# evpr_osh.net
KiCad netlist of a schematic drawn in EAGLE
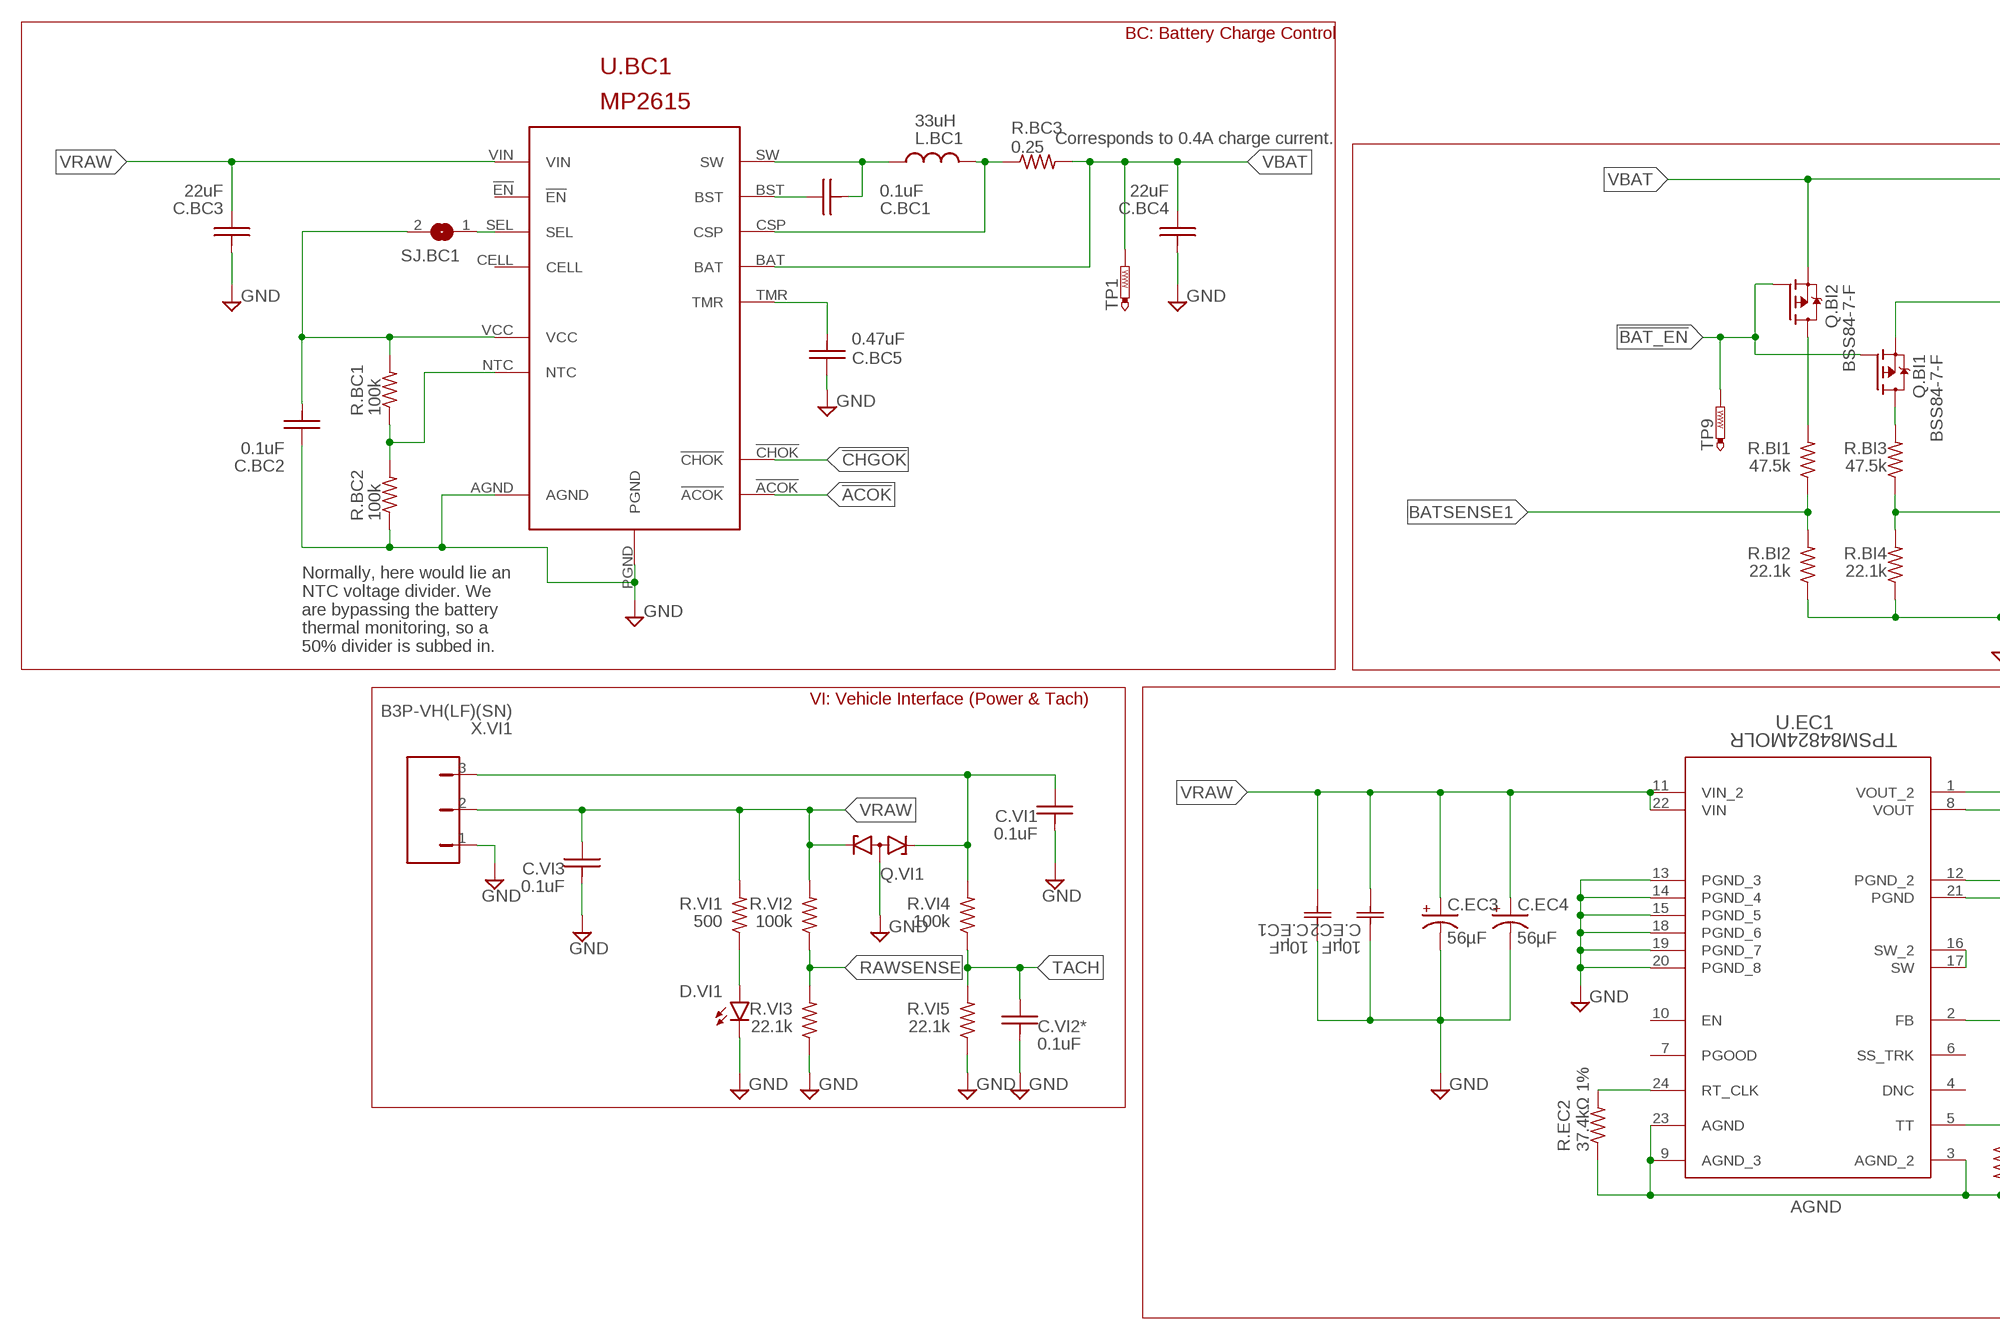
[diagram p0: schematic, sheet 1, part 1 of 2]
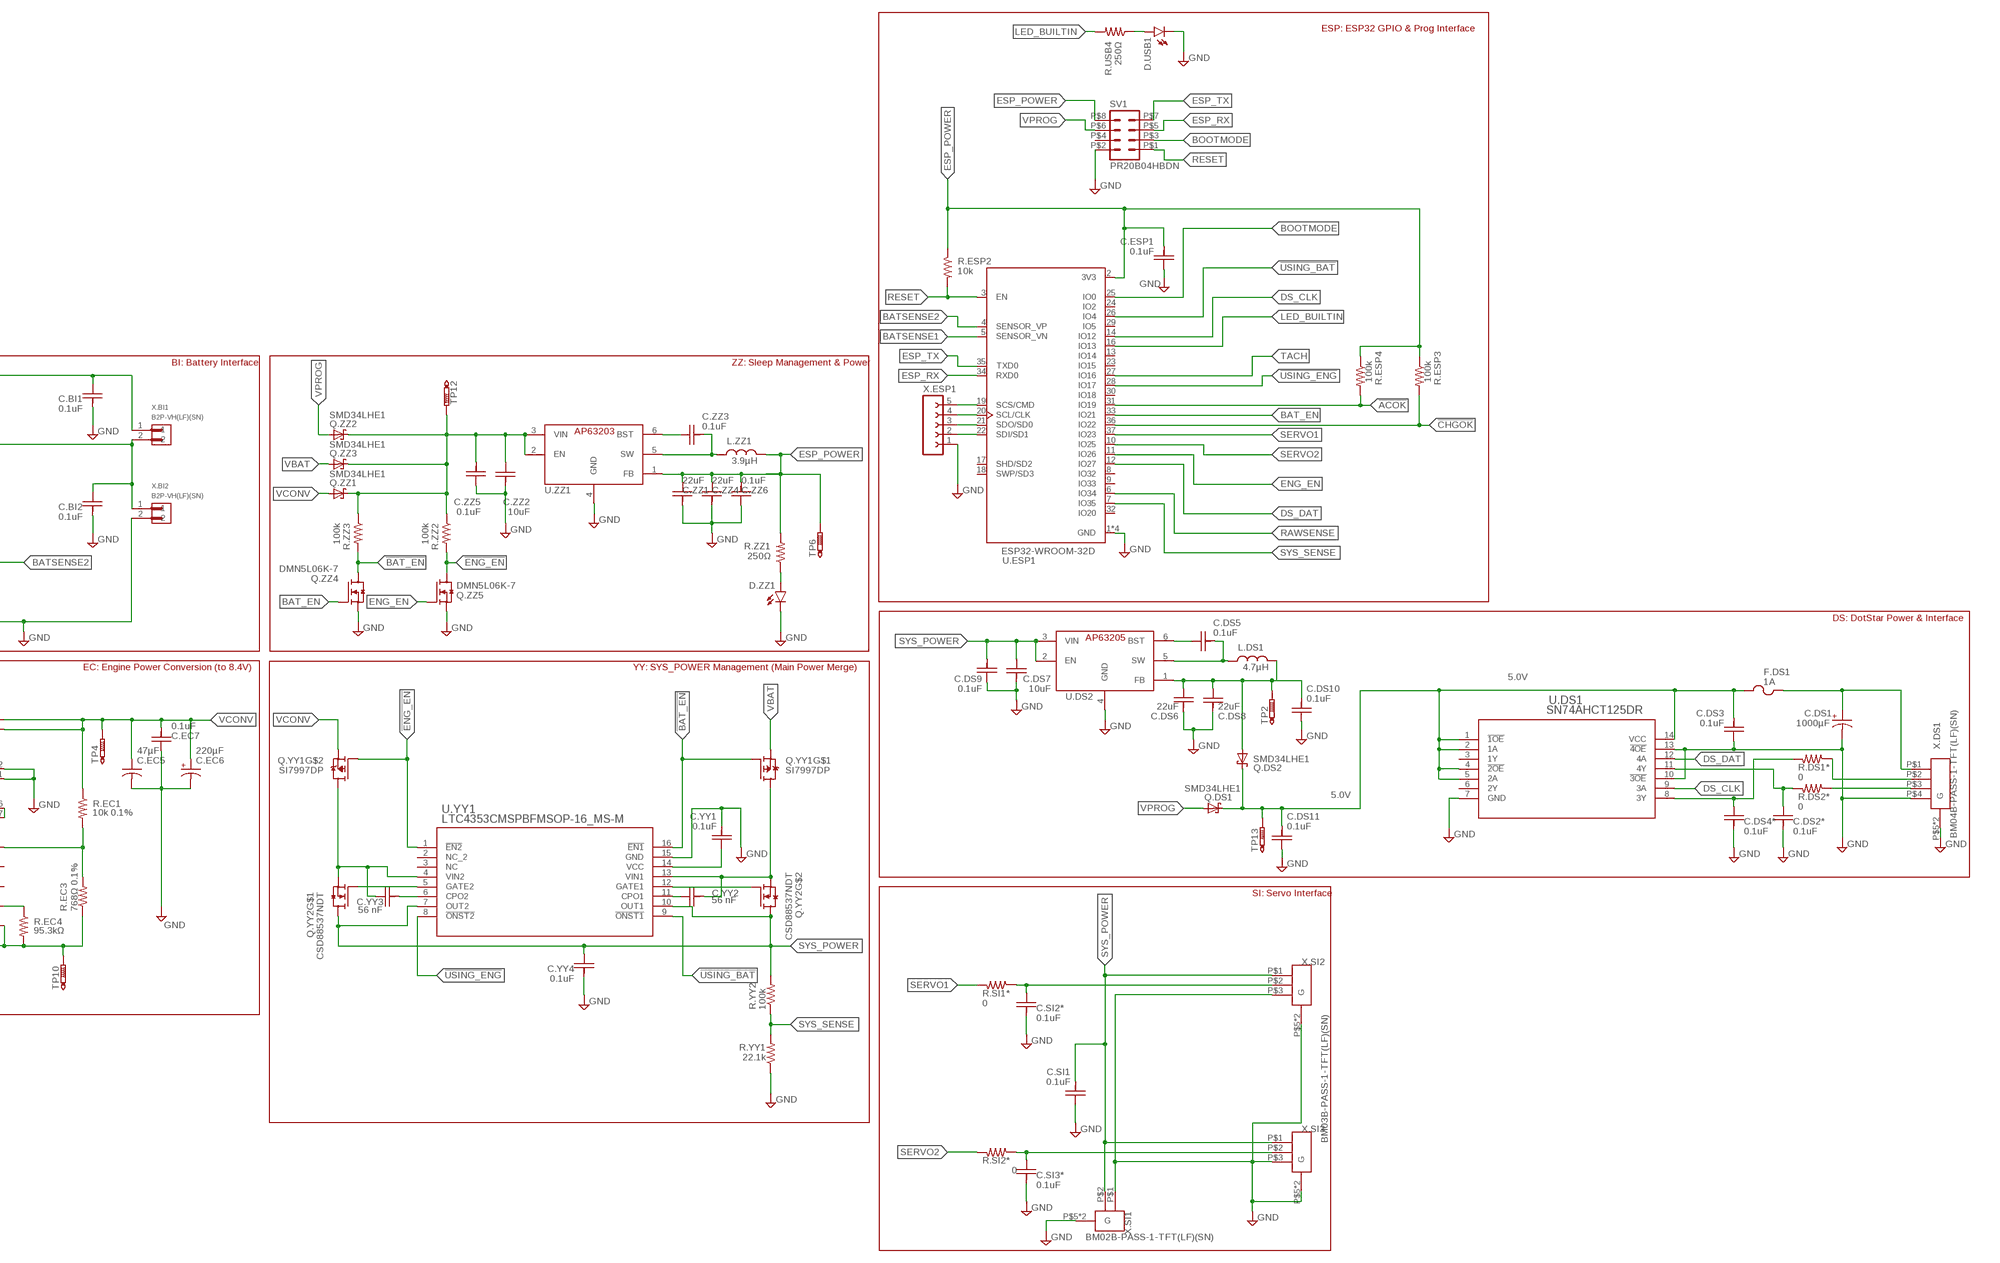
[diagram p1: schematic, sheet 1, part 2 of 2]

(export (version "E")
  (design (tool "Eeschema 10.0.6"))
  (components
    (comp (ref "C.BC1")
      (value "0.1uF")
      (footprint "eagle-import:C0603")
      (libsource (lib "eagle-import") (part "C0603"))
    )
    (comp (ref "C.BC2")
      (value "0.1uF")
      (footprint "eagle-import:C0603")
      (libsource (lib "eagle-import") (part "C0603"))
    )
    (comp (ref "C.BC3")
      (value "22uF")
      (footprint "eagle-import:C0603")
      (libsource (lib "eagle-import") (part "C0603"))
    )
    (comp (ref "C.BC4")
      (value "22uF")
      (footprint "eagle-import:C0603")
      (libsource (lib "eagle-import") (part "C0603"))
    )
    (comp (ref "C.BC5")
      (value "0.47uF")
      (footprint "eagle-import:C0603")
      (libsource (lib "eagle-import") (part "C0603"))
    )
    (comp (ref "C.BI1")
      (value "0.1uF")
      (footprint "eagle-import:C0603")
      (libsource (lib "eagle-import") (part "C0603"))
    )
    (comp (ref "C.BI2")
      (value "0.1uF")
      (footprint "eagle-import:C0603")
      (libsource (lib "eagle-import") (part "C0603"))
    )
    (comp (ref "C.DS1")
      (value "1000µF")
      (footprint "eagle-import:810RADCAN")
      (libsource (lib "eagle-import") (part "810RADCAP"))
    )
    (comp (ref "C.DS2*")
      (value "0.1uF")
      (footprint "eagle-import:C0603")
      (libsource (lib "eagle-import") (part "C0603"))
    )
    (comp (ref "C.DS3")
      (value "0.1uF")
      (footprint "eagle-import:C0603")
      (libsource (lib "eagle-import") (part "C0603"))
    )
    (comp (ref "C.DS4*")
      (value "0.1uF")
      (footprint "eagle-import:C0603")
      (libsource (lib "eagle-import") (part "C0603"))
    )
    (comp (ref "C.DS5")
      (value "0.1uF")
      (footprint "eagle-import:C0603")
      (libsource (lib "eagle-import") (part "C0603"))
    )
    (comp (ref "C.DS6")
      (value "22uF")
      (footprint "eagle-import:C0603")
      (libsource (lib "eagle-import") (part "C0603"))
    )
    (comp (ref "C.DS7")
      (value "10uF")
      (footprint "eagle-import:C0603")
      (libsource (lib "eagle-import") (part "C0603"))
    )
    (comp (ref "C.DS8")
      (value "22uF")
      (footprint "eagle-import:C0603")
      (libsource (lib "eagle-import") (part "C0603"))
    )
    (comp (ref "C.DS9")
      (value "0.1uF")
      (footprint "eagle-import:C0603")
      (libsource (lib "eagle-import") (part "C0603"))
    )
    (comp (ref "C.DS10")
      (value "0.1uF")
      (footprint "eagle-import:C0603")
      (libsource (lib "eagle-import") (part "C0603"))
    )
    (comp (ref "C.DS11")
      (value "0.1uF")
      (footprint "eagle-import:C0603")
      (libsource (lib "eagle-import") (part "C0603"))
    )
    (comp (ref "C.EC1")
      (value "10µF")
      (footprint "eagle-import:CAP_3225")
      (libsource (lib "eagle-import") (part "C3225X7R1E106K250AC"))
    )
    (comp (ref "C.EC2")
      (value "10µF")
      (footprint "eagle-import:CAP_3225")
      (libsource (lib "eagle-import") (part "C3225X7R1E106K250AC"))
    )
    (comp (ref "C.EC3")
      (value "56µF")
      (footprint "eagle-import:OSCON_SVPF_6.3MM")
      (libsource (lib "eagle-import") (part "6.3MMCAP"))
    )
    (comp (ref "C.EC4")
      (value "56µF")
      (footprint "eagle-import:OSCON_SVPF_6.3MM")
      (libsource (lib "eagle-import") (part "6.3MMCAP"))
    )
    (comp (ref "C.EC5")
      (value "47µF")
      (footprint "eagle-import:C1210")
      (libsource (lib "eagle-import") (part "C-USC1210"))
    )
    (comp (ref "C.EC6")
      (value "220µF")
      (footprint "eagle-import:C6CYLCAP")
      (libsource (lib "eagle-import") (part "WURTH875115352003"))
    )
    (comp (ref "C.EC7")
      (value "0.1uF")
      (footprint "eagle-import:C0603")
      (libsource (lib "eagle-import") (part "C0603"))
    )
    (comp (ref "C.ESP1")
      (value "0.1uF")
      (footprint "eagle-import:C0603")
      (libsource (lib "eagle-import") (part "C0603"))
    )
    (comp (ref "C.SI1")
      (value "0.1uF")
      (footprint "eagle-import:C0603")
      (libsource (lib "eagle-import") (part "C0603"))
    )
    (comp (ref "C.SI2*")
      (value "0.1uF")
      (footprint "eagle-import:C0603")
      (libsource (lib "eagle-import") (part "C0603"))
    )
    (comp (ref "C.SI3*")
      (value "0.1uF")
      (footprint "eagle-import:C0603")
      (libsource (lib "eagle-import") (part "C0603"))
    )
    (comp (ref "C.VI1")
      (value "0.1uF")
      (footprint "eagle-import:C0603")
      (libsource (lib "eagle-import") (part "C0603"))
    )
    (comp (ref "C.VI2*")
      (value "0.1uF")
      (footprint "eagle-import:C0603")
      (libsource (lib "eagle-import") (part "C0603"))
    )
    (comp (ref "C.VI3")
      (value "0.1uF")
      (footprint "eagle-import:C0603")
      (libsource (lib "eagle-import") (part "C0603"))
    )
    (comp (ref "C.YY1")
      (value "0.1uF")
      (footprint "eagle-import:C0603")
      (libsource (lib "eagle-import") (part "C0603"))
    )
    (comp (ref "C.YY2")
      (value "56 nF")
      (footprint "eagle-import:C0603")
      (libsource (lib "eagle-import") (part "C0603"))
    )
    (comp (ref "C.YY3")
      (value "56 nF")
      (footprint "eagle-import:C0603")
      (libsource (lib "eagle-import") (part "C0603"))
    )
    (comp (ref "C.YY4")
      (value "0.1uF")
      (footprint "eagle-import:C0603")
      (libsource (lib "eagle-import") (part "C0603"))
    )
    (comp (ref "C.ZZ1")
      (value "22uF")
      (footprint "eagle-import:C0603")
      (libsource (lib "eagle-import") (part "C0603"))
    )
    (comp (ref "C.ZZ2")
      (value "10uF")
      (footprint "eagle-import:C0603")
      (libsource (lib "eagle-import") (part "C0603"))
    )
    (comp (ref "C.ZZ3")
      (value "0.1uF")
      (footprint "eagle-import:C0603")
      (libsource (lib "eagle-import") (part "C0603"))
    )
    (comp (ref "C.ZZ4")
      (value "22uF")
      (footprint "eagle-import:C0603")
      (libsource (lib "eagle-import") (part "C0603"))
    )
    (comp (ref "C.ZZ5")
      (value "0.1uF")
      (footprint "eagle-import:C0603")
      (libsource (lib "eagle-import") (part "C0603"))
    )
    (comp (ref "C.ZZ6")
      (value "0.1uF")
      (footprint "eagle-import:C0603")
      (libsource (lib "eagle-import") (part "C0603"))
    )
    (comp (ref "D.USB1")
      (value "LEDCHIP-LED0805")
      (footprint "eagle-import:CHIP-LED0805")
      (libsource (lib "eagle-import") (part "LEDCHIP-LED0805"))
    )
    (comp (ref "D.VI1")
      (value "LEDCHIP-LED0805")
      (footprint "eagle-import:CHIP-LED0805")
      (libsource (lib "eagle-import") (part "LEDCHIP-LED0805"))
    )
    (comp (ref "D.ZZ1")
      (value "LEDCHIP-LED0805")
      (footprint "eagle-import:CHIP-LED0805")
      (libsource (lib "eagle-import") (part "LEDCHIP-LED0805"))
    )
    (comp (ref "F.DS1")
      (value "1A")
      (footprint "eagle-import:C1-M")
      (fields (field (name "MANUFACTURER_PART_NUMBER") "C1Q 1"))
      (libsource (lib "eagle-import") (part "C1Q_1C1-M"))
    )
    (comp (ref "L.BC1")
      (value "33uH")
      (footprint "eagle-import:SRN5040TA")
      (libsource (lib "eagle-import") (part "SRN5040TA-330M"))
    )
    (comp (ref "L.DS1")
      (value "4.7µH")
      (footprint "eagle-import:SRR4818A-XXXX")
      (libsource (lib "eagle-import") (part "SRR4818A-XXXX"))
    )
    (comp (ref "L.ZZ1")
      (value "3.9µH")
      (footprint "eagle-import:SRR4818A-XXXX")
      (libsource (lib "eagle-import") (part "SRR4818A-XXXX"))
    )
    (comp (ref "Q.BI1")
      (value "BSS84-7-F")
      (footprint "eagle-import:SOT23")
      (libsource (lib "eagle-import") (part "BSS84-7-F"))
    )
    (comp (ref "Q.BI2")
      (value "BSS84-7-F")
      (footprint "eagle-import:SOT23")
      (libsource (lib "eagle-import") (part "BSS84-7-F"))
    )
    (comp (ref "Q.DS1")
      (value "SMD34LHE1")
      (footprint "eagle-import:SOD-123HE1")
      (libsource (lib "eagle-import") (part "SMD34LHE1"))
    )
    (comp (ref "Q.DS2")
      (value "SMD34LHE1")
      (footprint "eagle-import:SOD-123HE1")
      (libsource (lib "eagle-import") (part "SMD34LHE1"))
    )
    (comp (ref "Q.VI1")
      (value "VESD16A2-03G-G3-08")
      (footprint "eagle-import:SOT23")
      (libsource (lib "eagle-import") (part "VESD16A2-03G-G3-08"))
    )
    (comp (ref "Q.YY1")
      (value "SI7997DP")
      (footprint "eagle-import:POWERPAK_SO8DUAL")
      (libsource (lib "eagle-import") (part "SI7997DP"))
    )
    (comp (ref "Q.YY2")
      (value "CSD88537NDT")
      (footprint "eagle-import:SOIC8")
      (fields (field (name "COMPONENT") "CSD88537NDT"))
      (libsource (lib "eagle-import") (part "CSD88537NDT"))
    )
    (comp (ref "Q.ZZ1")
      (value "SMD34LHE1")
      (footprint "eagle-import:SOD-123HE1")
      (libsource (lib "eagle-import") (part "SMD34LHE1"))
    )
    (comp (ref "Q.ZZ2")
      (value "SMD34LHE1")
      (footprint "eagle-import:SOD-123HE1")
      (libsource (lib "eagle-import") (part "SMD34LHE1"))
    )
    (comp (ref "Q.ZZ3")
      (value "SMD34LHE1")
      (footprint "eagle-import:SOD-123HE1")
      (libsource (lib "eagle-import") (part "SMD34LHE1"))
    )
    (comp (ref "Q.ZZ4")
      (value "DMN5L06K-7")
      (footprint "eagle-import:SOT23")
      (libsource (lib "eagle-import") (part "DMN5L06K-7"))
    )
    (comp (ref "Q.ZZ5")
      (value "DMN5L06K-7")
      (footprint "eagle-import:SOT23")
      (libsource (lib "eagle-import") (part "DMN5L06K-7"))
    )
    (comp (ref "R.BC1")
      (value "100k")
      (footprint "eagle-import:R0603")
      (libsource (lib "eagle-import") (part "R0603"))
    )
    (comp (ref "R.BC2")
      (value "100k")
      (footprint "eagle-import:R0603")
      (libsource (lib "eagle-import") (part "R0603"))
    )
    (comp (ref "R.BC3")
      (value "0.25")
      (footprint "eagle-import:R0603")
      (libsource (lib "eagle-import") (part "R0603"))
    )
    (comp (ref "R.BI1")
      (value "47.5k")
      (footprint "eagle-import:R0603")
      (libsource (lib "eagle-import") (part "R0603"))
    )
    (comp (ref "R.BI2")
      (value "22.1k")
      (footprint "eagle-import:R0603")
      (libsource (lib "eagle-import") (part "R0603"))
    )
    (comp (ref "R.BI3")
      (value "47.5k")
      (footprint "eagle-import:R0603")
      (libsource (lib "eagle-import") (part "R0603"))
    )
    (comp (ref "R.BI4")
      (value "22.1k")
      (footprint "eagle-import:R0603")
      (libsource (lib "eagle-import") (part "R0603"))
    )
    (comp (ref "R.DS1*")
      (value "0")
      (footprint "eagle-import:R0603")
      (libsource (lib "eagle-import") (part "R0603"))
    )
    (comp (ref "R.DS2*")
      (value "0")
      (footprint "eagle-import:R0603")
      (libsource (lib "eagle-import") (part "R0603"))
    )
    (comp (ref "R.EC1")
      (value "10k 0.1%")
      (footprint "eagle-import:R0603")
      (libsource (lib "eagle-import") (part "R0603"))
    )
    (comp (ref "R.EC2")
      (value "37.4kΩ 1%")
      (footprint "eagle-import:R0603")
      (libsource (lib "eagle-import") (part "R0603"))
    )
    (comp (ref "R.EC3")
      (value "768Ω 0.1%")
      (footprint "eagle-import:R0603")
      (libsource (lib "eagle-import") (part "R0603"))
    )
    (comp (ref "R.EC4")
      (value "95.3kΩ")
      (footprint "eagle-import:R0603")
      (libsource (lib "eagle-import") (part "R0603"))
    )
    (comp (ref "R.ESP2")
      (value "10k")
      (footprint "eagle-import:R0603")
      (libsource (lib "eagle-import") (part "R0603"))
    )
    (comp (ref "R.ESP3")
      (value "100k")
      (footprint "eagle-import:R0603")
      (libsource (lib "eagle-import") (part "R0603"))
    )
    (comp (ref "R.ESP4")
      (value "100k")
      (footprint "eagle-import:R0603")
      (libsource (lib "eagle-import") (part "R0603"))
    )
    (comp (ref "R.SI1*")
      (value "0")
      (footprint "eagle-import:R0603")
      (libsource (lib "eagle-import") (part "R0603"))
    )
    (comp (ref "R.SI2*")
      (value "0")
      (footprint "eagle-import:R0603")
      (libsource (lib "eagle-import") (part "R0603"))
    )
    (comp (ref "R.USB4")
      (value "250Ω")
      (footprint "eagle-import:R0603")
      (libsource (lib "eagle-import") (part "R0603"))
    )
    (comp (ref "R.VI1")
      (value "500")
      (footprint "eagle-import:R0603")
      (libsource (lib "eagle-import") (part "R0603"))
    )
    (comp (ref "R.VI2")
      (value "100k")
      (footprint "eagle-import:R0603")
      (libsource (lib "eagle-import") (part "R0603"))
    )
    (comp (ref "R.VI3")
      (value "22.1k")
      (footprint "eagle-import:R0603")
      (libsource (lib "eagle-import") (part "R0603"))
    )
    (comp (ref "R.VI4")
      (value "100k")
      (footprint "eagle-import:R0603")
      (libsource (lib "eagle-import") (part "R0603"))
    )
    (comp (ref "R.VI5")
      (value "22.1k")
      (footprint "eagle-import:R0603")
      (libsource (lib "eagle-import") (part "R0603"))
    )
    (comp (ref "R.YY1")
      (value "22.1k")
      (footprint "eagle-import:R0603")
      (libsource (lib "eagle-import") (part "R0603"))
    )
    (comp (ref "R.YY2")
      (value "100k")
      (footprint "eagle-import:R0603")
      (libsource (lib "eagle-import") (part "R0603"))
    )
    (comp (ref "R.ZZ1")
      (value "250Ω")
      (footprint "eagle-import:R0603")
      (libsource (lib "eagle-import") (part "R0603"))
    )
    (comp (ref "R.ZZ2")
      (value "100k")
      (footprint "eagle-import:R0603")
      (libsource (lib "eagle-import") (part "R0603"))
    )
    (comp (ref "R.ZZ3")
      (value "100k")
      (footprint "eagle-import:R0603")
      (libsource (lib "eagle-import") (part "R0603"))
    )
    (comp (ref "SJ.BC1")
      (value "SJ")
      (footprint "eagle-import:SJ")
      (libsource (lib "eagle-import") (part "SJ"))
    )
    (comp (ref "SV1")
      (value "PR20B04HBDN")
      (footprint "eagle-import:PR20B04HBDN")
      (libsource (lib "eagle-import") (part "PR20B04HBDN"))
    )
    (comp (ref "TP1")
      (value "PTR1TP10R")
      (footprint "eagle-import:TP10R")
      (libsource (lib "eagle-import") (part "PTR1TP10R"))
    )
    (comp (ref "TP2")
      (value "PTR1TP10R")
      (footprint "eagle-import:TP10R")
      (libsource (lib "eagle-import") (part "PTR1TP10R"))
    )
    (comp (ref "TP4")
      (value "PTR1TP10R")
      (footprint "eagle-import:TP10R")
      (libsource (lib "eagle-import") (part "PTR1TP10R"))
    )
    (comp (ref "TP6")
      (value "PTR1TP10R")
      (footprint "eagle-import:TP10R")
      (libsource (lib "eagle-import") (part "PTR1TP10R"))
    )
    (comp (ref "TP9")
      (value "PTR1TP10R")
      (footprint "eagle-import:TP10R")
      (libsource (lib "eagle-import") (part "PTR1TP10R"))
    )
    (comp (ref "TP10")
      (value "PTR1TP10R")
      (footprint "eagle-import:TP10R")
      (libsource (lib "eagle-import") (part "PTR1TP10R"))
    )
    (comp (ref "TP12")
      (value "PTR1TP10R")
      (footprint "eagle-import:TP10R")
      (libsource (lib "eagle-import") (part "PTR1TP10R"))
    )
    (comp (ref "TP13")
      (value "PTR1TP10R")
      (footprint "eagle-import:TP10R")
      (libsource (lib "eagle-import") (part "PTR1TP10R"))
    )
    (comp (ref "U.BC1")
      (value "MP2615")
      (footprint "eagle-import:QFN16")
      (libsource (lib "eagle-import") (part "MP2615"))
    )
    (comp (ref "U.DS1")
      (value "SN74AHCT125DR")
      (footprint "eagle-import:D14")
      (libsource (lib "eagle-import") (part "SN74AHCT125DR"))
    )
    (comp (ref "U.DS2")
      (value "AP63205")
      (footprint "eagle-import:TSOT23-6")
      (libsource (lib "eagle-import") (part "AP63205"))
    )
    (comp (ref "U.EC1")
      (value "TPSM84824MOLR")
      (footprint "eagle-import:MOL0024A")
      (libsource (lib "eagle-import") (part "TPSM84824MOLR"))
    )
    (comp (ref "U.ESP1")
      (value "ESP32-WROOM-32D")
      (footprint "eagle-import:MODULE_ESP32-WROOM-32D")
      (fields (field (name "MF") "Espressif Systems"))
      (libsource (lib "eagle-import") (part "ESP32-WROOM-32D"))
    )
    (comp (ref "U.YY1")
      (value "LTC4353CMSPBFMSOP-16_MS-M")
      (footprint "eagle-import:MSOP-16_MS-M")
      (fields (field (name "MANUFACTURER_PART_NUMBER") "LTC4353CMS#PBF"))
      (libsource (lib "eagle-import") (part "LTC4353CMSPBFMSOP-16_MS-M"))
    )
    (comp (ref "U.ZZ1")
      (value "AP63203")
      (footprint "eagle-import:TSOT23-6")
      (libsource (lib "eagle-import") (part "AP63203"))
    )
    (comp (ref "X.BI1")
      (value "B2P-VH(LF)(SN)")
      (footprint "eagle-import:JST_B2P-VH(LF)(SN)")
      (fields (field (name "MF") "JST Sales") (field (name "MP") "B2P-VH_LF__SN_"))
      (libsource (lib "eagle-import") (part "B2P-VH(LF)(SN)"))
    )
    (comp (ref "X.BI2")
      (value "B2P-VH(LF)(SN)")
      (footprint "eagle-import:JST_B2P-VH(LF)(SN)")
      (fields (field (name "MF") "JST Sales") (field (name "MP") "B2P-VH_LF__SN_"))
      (libsource (lib "eagle-import") (part "B2P-VH(LF)(SN)"))
    )
    (comp (ref "X.DS1")
      (value "BM04B-PASS-1-TFT(LF)(SN)")
      (footprint "eagle-import:BM04B-PASS-1-TFT(LF)(SN)")
      (libsource (lib "eagle-import") (part "BM04B-PASS-1-TFT(LF)(SN)"))
    )
    (comp (ref "X.ESP1")
      (value "FE05-1")
      (footprint "eagle-import:FE05-1")
      (libsource (lib "eagle-import") (part "FE05-1"))
    )
    (comp (ref "X.SI1")
      (value "BM02B-PASS-1-TFT(LF)(SN)")
      (footprint "eagle-import:BM02B-PASS-1-TFT(LF)(SN)")
      (libsource (lib "eagle-import") (part "BM02B-PASS-1-TFT(LF)(SN)"))
    )
    (comp (ref "X.SI2")
      (value "BM03B-PASS-1-TFT(LF)(SN)")
      (footprint "eagle-import:BM03B-PASS-1-TFT(LF)(SN)")
      (libsource (lib "eagle-import") (part "BM03B-PASS-1-TFT(LF)(SN)"))
    )
    (comp (ref "X.SI3")
      (value "BM03B-PASS-1-TFT(LF)(SN)")
      (footprint "eagle-import:BM03B-PASS-1-TFT(LF)(SN)")
      (libsource (lib "eagle-import") (part "BM03B-PASS-1-TFT(LF)(SN)"))
    )
    (comp (ref "X.VI1")
      (value "B3P-VH(LF)(SN)")
      (footprint "eagle-import:B3P-VH")
      (fields (field (name "MF") "JST Sales") (field (name "MP") "B3P-VH_LF__SN_"))
      (libsource (lib "eagle-import") (part "B3P-VH(LF)(SN)"))
    )
  )
  (nets
    (net (code "1") (name "/5.0V") (class "Default")
      (node (ref "C.DS11") (pin "2") (pinfunction "2_2") (pintype "passive"))
      (node (ref "C.DS3") (pin "2") (pinfunction "2_2") (pintype "passive"))
      (node (ref "F.DS1") (pin "1") (pinfunction "1_1") (pintype "passive"))
      (node (ref "Q.DS1") (pin "C") (pinfunction "C_C") (pintype "passive"))
      (node (ref "Q.DS2") (pin "C") (pinfunction "C_C") (pintype "passive"))
      (node (ref "TP13") (pin "TP") (pinfunction "TP_TP") (pintype "input"))
      (node (ref "U.DS1") (pin "1") (pinfunction "~{1OE}_1") (pintype "input"))
      (node (ref "U.DS1") (pin "14") (pinfunction "VCC_14") (pintype "power_in"))
      (node (ref "U.DS1") (pin "2") (pinfunction "1A_2") (pintype "input"))
      (node (ref "U.DS1") (pin "4") (pinfunction "~{2OE}_4") (pintype "input"))
      (node (ref "U.DS1") (pin "5") (pinfunction "2A_5") (pintype "input"))
    )
    (net (code "2") (name "/AGND") (class "Default")
      (node (ref "R.EC2") (pin "1") (pinfunction "1_1") (pintype "passive"))
      (node (ref "R.EC3") (pin "1") (pinfunction "1_1") (pintype "passive"))
      (node (ref "R.EC4") (pin "2") (pinfunction "2_2") (pintype "passive"))
      (node (ref "TP10") (pin "TP") (pinfunction "TP_TP") (pintype "input"))
      (node (ref "U.EC1") (pin "23") (pinfunction "AGND_23") (pintype "power_in"))
      (node (ref "U.EC1") (pin "3") (pinfunction "AGND_2_3") (pintype "power_in"))
      (node (ref "U.EC1") (pin "9") (pinfunction "AGND_3_9") (pintype "power_in"))
    )
    (net (code "3") (name "/~{ACOK}") (class "Default")
      (node (ref "R.ESP4") (pin "2") (pinfunction "2_2") (pintype "passive"))
      (node (ref "U.BC1") (pin "!ACOK") (pinfunction "~{ACOK}_!ACOK") (pintype "bidirectional"))
      (node (ref "U.ESP1") (pin "31") (pinfunction "IO19_31") (pintype "bidirectional"))
    )
    (net (code "4") (name "/~{BAT_EN}") (class "Default")
      (node (ref "Q.BI1") (pin "1") (pinfunction "G_1") (pintype "passive"))
      (node (ref "Q.BI2") (pin "1") (pinfunction "G_1") (pintype "passive"))
      (node (ref "Q.YY1") (pin "P$2") (pinfunction "G_P$2") (pintype "passive"))
      (node (ref "Q.ZZ4") (pin "3") (pinfunction "D_3") (pintype "passive"))
      (node (ref "R.ZZ3") (pin "2") (pinfunction "2_2") (pintype "passive"))
      (node (ref "TP9") (pin "TP") (pinfunction "TP_TP") (pintype "input"))
      (node (ref "U.YY1") (pin "16") (pinfunction "~{EN1}_16") (pintype "input"))
    )
    (net (code "5") (name "/~{CHGOK}") (class "Default")
      (node (ref "R.ESP3") (pin "2") (pinfunction "2_2") (pintype "passive"))
      (node (ref "U.BC1") (pin "!CHOK") (pinfunction "~{CHOK}_!CHOK") (pintype "bidirectional"))
      (node (ref "U.ESP1") (pin "36") (pinfunction "IO22_36") (pintype "bidirectional"))
    )
    (net (code "6") (name "/~{ENG_EN}") (class "Default")
      (node (ref "Q.YY1") (pin "P$4") (pinfunction "G_P$4") (pintype "passive"))
      (node (ref "Q.ZZ5") (pin "3") (pinfunction "D_3") (pintype "passive"))
      (node (ref "R.ZZ2") (pin "2") (pinfunction "2_2") (pintype "passive"))
      (node (ref "U.YY1") (pin "1") (pinfunction "~{EN2}_1") (pintype "input"))
    )
    (net (code "7") (name "/~{USING_BAT}") (class "Default")
      (node (ref "U.ESP1") (pin "26") (pinfunction "IO4_26") (pintype "bidirectional"))
      (node (ref "U.YY1") (pin "9") (pinfunction "~{ONST1}_9") (pintype "output"))
    )
    (net (code "8") (name "/~{USING_ENG}") (class "Default")
      (node (ref "U.ESP1") (pin "28") (pinfunction "IO17_28") (pintype "bidirectional"))
      (node (ref "U.YY1") (pin "8") (pinfunction "~{ONST2}_8") (pintype "output"))
    )
    (net (code "9") (name "BATSENSE1") (class "Default")
      (node (ref "R.BI1") (pin "1") (pinfunction "1_1") (pintype "passive"))
      (node (ref "R.BI2") (pin "2") (pinfunction "2_2") (pintype "passive"))
      (node (ref "U.ESP1") (pin "5") (pinfunction "SENSOR_VN_5") (pintype "input"))
    )
    (net (code "10") (name "BATSENSE2") (class "Default")
      (node (ref "R.BI3") (pin "1") (pinfunction "1_1") (pintype "passive"))
      (node (ref "R.BI4") (pin "2") (pinfunction "2_2") (pintype "passive"))
      (node (ref "U.ESP1") (pin "4") (pinfunction "SENSOR_VP_4") (pintype "input"))
    )
    (net (code "11") (name "BAT_EN") (class "Default")
      (node (ref "Q.ZZ4") (pin "1") (pinfunction "G_1") (pintype "passive"))
      (node (ref "U.ESP1") (pin "33") (pinfunction "IO21_33") (pintype "bidirectional"))
    )
    (net (code "12") (name "BOOTMODE") (class "Default")
      (node (ref "SV1") (pin "P$3") (pinfunction "3_P$3") (pintype "passive"))
      (node (ref "U.ESP1") (pin "25") (pinfunction "IO0_25") (pintype "bidirectional"))
    )
    (net (code "13") (name "DS_CLK") (class "Default")
      (node (ref "U.DS1") (pin "9") (pinfunction "3A_9") (pintype "input"))
      (node (ref "U.ESP1") (pin "14") (pinfunction "IO12_14") (pintype "bidirectional"))
    )
    (net (code "14") (name "DS_DAT") (class "Default")
      (node (ref "U.DS1") (pin "12") (pinfunction "4A_12") (pintype "input"))
      (node (ref "U.ESP1") (pin "12") (pinfunction "IO27_12") (pintype "bidirectional"))
    )
    (net (code "15") (name "ENG_EN") (class "Default")
      (node (ref "Q.ZZ5") (pin "1") (pinfunction "G_1") (pintype "passive"))
      (node (ref "U.ESP1") (pin "11") (pinfunction "IO26_11") (pintype "bidirectional"))
    )
    (net (code "16") (name "ESP_POWER") (class "Default")
      (node (ref "C.ESP1") (pin "2") (pinfunction "2_2") (pintype "passive"))
      (node (ref "C.ZZ1") (pin "1") (pinfunction "1_1") (pintype "passive"))
      (node (ref "C.ZZ4") (pin "1") (pinfunction "1_1") (pintype "passive"))
      (node (ref "C.ZZ6") (pin "2") (pinfunction "2_2") (pintype "passive"))
      (node (ref "L.ZZ1") (pin "P$2") (pinfunction "2_P$2") (pintype "passive"))
      (node (ref "R.ESP2") (pin "1") (pinfunction "1_1") (pintype "passive"))
      (node (ref "R.ESP3") (pin "1") (pinfunction "1_1") (pintype "passive"))
      (node (ref "R.ESP4") (pin "1") (pinfunction "1_1") (pintype "passive"))
      (node (ref "R.ZZ1") (pin "2") (pinfunction "2_2") (pintype "passive"))
      (node (ref "SV1") (pin "P$8") (pinfunction "8_P$8") (pintype "passive"))
      (node (ref "TP6") (pin "TP") (pinfunction "TP_TP") (pintype "input"))
      (node (ref "U.ESP1") (pin "2") (pinfunction "3V3_2") (pintype "power_in"))
      (node (ref "U.ZZ1") (pin "1") (pinfunction "FB_1") (pintype "bidirectional"))
    )
    (net (code "17") (name "ESP_RX") (class "Default")
      (node (ref "SV1") (pin "P$5") (pinfunction "5_P$5") (pintype "passive"))
      (node (ref "U.ESP1") (pin "34") (pinfunction "RXD0_34") (pintype "bidirectional"))
    )
    (net (code "18") (name "ESP_TX") (class "Default")
      (node (ref "SV1") (pin "P$7") (pinfunction "7_P$7") (pintype "passive"))
      (node (ref "U.ESP1") (pin "35") (pinfunction "TXD0_35") (pintype "bidirectional"))
    )
    (net (code "19") (name "GND") (class "Default")
      (node (ref "C.BC2") (pin "1") (pinfunction "1_1") (pintype "passive"))
      (node (ref "C.BC3") (pin "2") (pinfunction "2_2") (pintype "passive"))
      (node (ref "C.BC4") (pin "2") (pinfunction "2_2") (pintype "passive"))
      (node (ref "C.BC5") (pin "1") (pinfunction "1_1") (pintype "passive"))
      (node (ref "C.BI1") (pin "2") (pinfunction "2_2") (pintype "passive"))
      (node (ref "C.BI2") (pin "2") (pinfunction "2_2") (pintype "passive"))
      (node (ref "C.DS1") (pin "C$2") (pinfunction "-_C$2") (pintype "passive"))
      (node (ref "C.DS10") (pin "1") (pinfunction "1_1") (pintype "passive"))
      (node (ref "C.DS11") (pin "1") (pinfunction "1_1") (pintype "passive"))
      (node (ref "C.DS2*") (pin "2") (pinfunction "2_2") (pintype "passive"))
      (node (ref "C.DS3") (pin "1") (pinfunction "1_1") (pintype "passive"))
      (node (ref "C.DS4*") (pin "2") (pinfunction "2_2") (pintype "passive"))
      (node (ref "C.DS6") (pin "2") (pinfunction "2_2") (pintype "passive"))
      (node (ref "C.DS7") (pin "2") (pinfunction "2_2") (pintype "passive"))
      (node (ref "C.DS8") (pin "2") (pinfunction "2_2") (pintype "passive"))
      (node (ref "C.DS9") (pin "1") (pinfunction "1_1") (pintype "passive"))
      (node (ref "C.EC1") (pin "1") (pinfunction "1_1") (pintype "passive"))
      (node (ref "C.EC2") (pin "1") (pinfunction "1_1") (pintype "passive"))
      (node (ref "C.EC3") (pin "-") (pinfunction "-_-") (pintype "passive"))
      (node (ref "C.EC4") (pin "-") (pinfunction "-_-") (pintype "passive"))
      (node (ref "C.EC5") (pin "2") (pinfunction "2_2") (pintype "passive"))
      (node (ref "C.EC6") (pin "P$1") (pinfunction "-_P$1") (pintype "passive"))
      (node (ref "C.EC7") (pin "1") (pinfunction "1_1") (pintype "passive"))
      (node (ref "C.ESP1") (pin "1") (pinfunction "1_1") (pintype "passive"))
      (node (ref "C.SI1") (pin "1") (pinfunction "1_1") (pintype "passive"))
      (node (ref "C.SI2*") (pin "2") (pinfunction "2_2") (pintype "passive"))
      (node (ref "C.SI3*") (pin "2") (pinfunction "2_2") (pintype "passive"))
      (node (ref "C.VI1") (pin "2") (pinfunction "2_2") (pintype "passive"))
      (node (ref "C.VI2*") (pin "2") (pinfunction "2_2") (pintype "passive"))
      (node (ref "C.VI3") (pin "2") (pinfunction "2_2") (pintype "passive"))
      (node (ref "C.YY1") (pin "2") (pinfunction "2_2") (pintype "passive"))
      (node (ref "C.YY4") (pin "2") (pinfunction "2_2") (pintype "passive"))
      (node (ref "C.ZZ1") (pin "2") (pinfunction "2_2") (pintype "passive"))
      (node (ref "C.ZZ2") (pin "2") (pinfunction "2_2") (pintype "passive"))
      (node (ref "C.ZZ4") (pin "2") (pinfunction "2_2") (pintype "passive"))
      (node (ref "C.ZZ5") (pin "1") (pinfunction "1_1") (pintype "passive"))
      (node (ref "C.ZZ6") (pin "1") (pinfunction "1_1") (pintype "passive"))
      (node (ref "D.USB1") (pin "C") (pinfunction "C_C") (pintype "passive"))
      (node (ref "D.VI1") (pin "C") (pinfunction "C_C") (pintype "passive"))
      (node (ref "D.ZZ1") (pin "C") (pinfunction "C_C") (pintype "passive"))
      (node (ref "Q.VI1") (pin "3") (pinfunction "AA_3") (pintype "passive"))
      (node (ref "Q.ZZ4") (pin "2") (pinfunction "S_2") (pintype "passive"))
      (node (ref "Q.ZZ5") (pin "2") (pinfunction "S_2") (pintype "passive"))
      (node (ref "R.BC2") (pin "1") (pinfunction "1_1") (pintype "passive"))
      (node (ref "R.BI2") (pin "1") (pinfunction "1_1") (pintype "passive"))
      (node (ref "R.BI4") (pin "1") (pinfunction "1_1") (pintype "passive"))
      (node (ref "R.VI3") (pin "1") (pinfunction "1_1") (pintype "passive"))
      (node (ref "R.VI5") (pin "1") (pinfunction "1_1") (pintype "passive"))
      (node (ref "R.YY1") (pin "1") (pinfunction "1_1") (pintype "passive"))
      (node (ref "SV1") (pin "P$2") (pinfunction "2_P$2") (pintype "passive"))
      (node (ref "U.BC1") (pin "AGND") (pinfunction "AGND_AGND") (pintype "bidirectional"))
      (node (ref "U.BC1") (pin "PGND") (pinfunction "PGND_PGND") (pintype "bidirectional"))
      (node (ref "U.DS1") (pin "10") (pinfunction "~{3OE}_10") (pintype "input"))
      (node (ref "U.DS1") (pin "13") (pinfunction "~{4OE}_13") (pintype "input"))
      (node (ref "U.DS1") (pin "7") (pinfunction "GND_7") (pintype "power_in"))
      (node (ref "U.DS2") (pin "4") (pinfunction "GND_4") (pintype "bidirectional"))
      (node (ref "U.EC1") (pin "12") (pinfunction "PGND_2_12") (pintype "power_in"))
      (node (ref "U.EC1") (pin "13") (pinfunction "PGND_3_13") (pintype "power_in"))
      (node (ref "U.EC1") (pin "14") (pinfunction "PGND_4_14") (pintype "power_in"))
      (node (ref "U.EC1") (pin "15") (pinfunction "PGND_5_15") (pintype "power_in"))
      (node (ref "U.EC1") (pin "18") (pinfunction "PGND_6_18") (pintype "power_in"))
      (node (ref "U.EC1") (pin "19") (pinfunction "PGND_7_19") (pintype "power_in"))
      (node (ref "U.EC1") (pin "20") (pinfunction "PGND_8_20") (pintype "power_in"))
      (node (ref "U.EC1") (pin "21") (pinfunction "PGND_21") (pintype "power_in"))
      (node (ref "U.ESP1") (pin "1") (pinfunction "GND_1") (pintype "power_in"))
      (node (ref "U.ESP1") (pin "15") (pinfunction "GND_15") (pintype "power_in"))
      (node (ref "U.ESP1") (pin "38") (pinfunction "GND_38") (pintype "power_in"))
      (node (ref "U.ESP1") (pin "39") (pinfunction "GND_39") (pintype "power_in"))
      (node (ref "U.YY1") (pin "15") (pinfunction "GND_15") (pintype "power_in"))
      (node (ref "U.ZZ1") (pin "4") (pinfunction "GND_4") (pintype "bidirectional"))
      (node (ref "X.BI2") (pin "2") (pinfunction "2_2") (pintype "passive"))
      (node (ref "X.DS1") (pin "P$4") (pinfunction "4_P$4") (pintype "passive"))
      (node (ref "X.DS1") (pin "P$5") (pinfunction "G_P$5") (pintype "passive"))
      (node (ref "X.DS1") (pin "P$6") (pinfunction "G_P$6") (pintype "passive"))
      (node (ref "X.ESP1") (pin "1") (pinfunction "1_1") (pintype "passive"))
      (node (ref "X.SI1") (pin "P$1") (pinfunction "1_P$1") (pintype "passive"))
      (node (ref "X.SI1") (pin "P$5") (pinfunction "G_P$5") (pintype "passive"))
      (node (ref "X.SI1") (pin "P$6") (pinfunction "G_P$6") (pintype "passive"))
      (node (ref "X.SI2") (pin "P$3") (pinfunction "3_P$3") (pintype "passive"))
      (node (ref "X.SI2") (pin "P$5") (pinfunction "G_P$5") (pintype "passive"))
      (node (ref "X.SI2") (pin "P$6") (pinfunction "G_P$6") (pintype "passive"))
      (node (ref "X.SI3") (pin "P$3") (pinfunction "3_P$3") (pintype "passive"))
      (node (ref "X.SI3") (pin "P$5") (pinfunction "G_P$5") (pintype "passive"))
      (node (ref "X.SI3") (pin "P$6") (pinfunction "G_P$6") (pintype "passive"))
      (node (ref "X.VI1") (pin "1") (pinfunction "1_1") (pintype "passive"))
    )
    (net (code "20") (name "LED_BUILTIN") (class "Default")
      (node (ref "R.USB4") (pin "2") (pinfunction "2_2") (pintype "passive"))
      (node (ref "U.ESP1") (pin "16") (pinfunction "IO13_16") (pintype "bidirectional"))
    )
    (net (code "21") (name "Net-(C.BC1-Pad1)") (class "Default")
      (node (ref "C.BC1") (pin "1") (pinfunction "1_1") (pintype "passive"))
      (node (ref "U.BC1") (pin "BST") (pinfunction "BST_BST") (pintype "bidirectional"))
    )
    (net (code "22") (name "Net-(C.BC2-Pad2)") (class "Default")
      (node (ref "C.BC2") (pin "2") (pinfunction "2_2") (pintype "passive"))
      (node (ref "R.BC1") (pin "2") (pinfunction "2_2") (pintype "passive"))
      (node (ref "SJ.BC1") (pin "2") (pinfunction "2_2") (pintype "passive"))
      (node (ref "U.BC1") (pin "VCC") (pinfunction "VCC_VCC") (pintype "bidirectional"))
    )
    (net (code "23") (name "Net-(C.BC5-Pad2)") (class "Default")
      (node (ref "C.BC5") (pin "2") (pinfunction "2_2") (pintype "passive"))
      (node (ref "U.BC1") (pin "TMR") (pinfunction "TMR_TMR") (pintype "bidirectional"))
    )
    (net (code "24") (name "Net-(C.DS1-+)") (class "Default")
      (node (ref "C.DS1") (pin "A$1") (pinfunction "+_A$1") (pintype "passive"))
      (node (ref "F.DS1") (pin "2") (pinfunction "2_2") (pintype "passive"))
      (node (ref "X.DS1") (pin "P$1") (pinfunction "1_P$1") (pintype "passive"))
    )
    (net (code "25") (name "Net-(D.USB1-PadA)") (class "Default")
      (node (ref "D.USB1") (pin "A") (pinfunction "A_A") (pintype "passive"))
      (node (ref "R.USB4") (pin "1") (pinfunction "1_1") (pintype "passive"))
    )
    (net (code "26") (name "Net-(D.VI1-PadA)") (class "Default")
      (node (ref "D.VI1") (pin "A") (pinfunction "A_A") (pintype "passive"))
      (node (ref "R.VI1") (pin "1") (pinfunction "1_1") (pintype "passive"))
    )
    (net (code "27") (name "Net-(D.ZZ1-PadA)") (class "Default")
      (node (ref "D.ZZ1") (pin "A") (pinfunction "A_A") (pintype "passive"))
      (node (ref "R.ZZ1") (pin "1") (pinfunction "1_1") (pintype "passive"))
    )
    (net (code "28") (name "Net-(L.BC1-1)") (class "Default")
      (node (ref "C.BC1") (pin "2") (pinfunction "2_2") (pintype "passive"))
      (node (ref "L.BC1") (pin "P$1") (pinfunction "1_P$1") (pintype "passive"))
      (node (ref "U.BC1") (pin "SW") (pinfunction "SW_SW") (pintype "bidirectional"))
    )
    (net (code "29") (name "Net-(L.BC1-2)") (class "Default")
      (node (ref "L.BC1") (pin "P$2") (pinfunction "2_P$2") (pintype "passive"))
      (node (ref "R.BC3") (pin "1") (pinfunction "1_1") (pintype "passive"))
      (node (ref "U.BC1") (pin "CSP") (pinfunction "CSP_CSP") (pintype "bidirectional"))
    )
    (net (code "30") (name "Net-(L.DS1-1)") (class "Default")
      (node (ref "C.DS5") (pin "2") (pinfunction "2_2") (pintype "passive"))
      (node (ref "L.DS1") (pin "P$1") (pinfunction "1_P$1") (pintype "passive"))
      (node (ref "U.DS2") (pin "5") (pinfunction "SW_5") (pintype "bidirectional"))
    )
    (net (code "31") (name "Net-(L.DS1-2)") (class "Default")
      (node (ref "C.DS10") (pin "2") (pinfunction "2_2") (pintype "passive"))
      (node (ref "C.DS6") (pin "1") (pinfunction "1_1") (pintype "passive"))
      (node (ref "C.DS8") (pin "1") (pinfunction "1_1") (pintype "passive"))
      (node (ref "L.DS1") (pin "P$2") (pinfunction "2_P$2") (pintype "passive"))
      (node (ref "Q.DS2") (pin "A") (pinfunction "A_A") (pintype "passive"))
      (node (ref "TP2") (pin "TP") (pinfunction "TP_TP") (pintype "input"))
      (node (ref "U.DS2") (pin "1") (pinfunction "FB_1") (pintype "bidirectional"))
    )
    (net (code "32") (name "Net-(L.ZZ1-1)") (class "Default")
      (node (ref "C.ZZ3") (pin "2") (pinfunction "2_2") (pintype "passive"))
      (node (ref "L.ZZ1") (pin "P$1") (pinfunction "1_P$1") (pintype "passive"))
      (node (ref "U.ZZ1") (pin "5") (pinfunction "SW_5") (pintype "bidirectional"))
    )
    (net (code "33") (name "Net-(Q.BI1-D)") (class "Default")
      (node (ref "Q.BI1") (pin "3") (pinfunction "D_3") (pintype "passive"))
      (node (ref "R.BI3") (pin "2") (pinfunction "2_2") (pintype "passive"))
    )
    (net (code "34") (name "Net-(Q.BI1-S)") (class "Default")
      (node (ref "C.BI2") (pin "1") (pinfunction "1_1") (pintype "passive"))
      (node (ref "Q.BI1") (pin "2") (pinfunction "S_2") (pintype "passive"))
      (node (ref "X.BI1") (pin "2") (pinfunction "2_2") (pintype "passive"))
      (node (ref "X.BI2") (pin "1") (pinfunction "1_1") (pintype "passive"))
    )
    (net (code "35") (name "Net-(Q.BI2-D)") (class "Default")
      (node (ref "Q.BI2") (pin "3") (pinfunction "D_3") (pintype "passive"))
      (node (ref "R.BI1") (pin "2") (pinfunction "2_2") (pintype "passive"))
    )
    (net (code "36") (name "Net-(Q.VI1-K1)") (class "Default")
      (node (ref "C.VI1") (pin "1") (pinfunction "1_1") (pintype "passive"))
      (node (ref "Q.VI1") (pin "2") (pinfunction "K1_2") (pintype "passive"))
      (node (ref "R.VI4") (pin "2") (pinfunction "2_2") (pintype "passive"))
      (node (ref "X.VI1") (pin "3") (pinfunction "3_3") (pintype "passive"))
    )
    (net (code "37") (name "Net-(Q.YY1A-D)") (class "Default")
      (node (ref "C.YY2") (pin "2") (pinfunction "2_2") (pintype "passive"))
      (node (ref "Q.YY1") (pin "D$1B") (pinfunction "D_D$1B") (pintype "passive"))
      (node (ref "Q.YY2") (pin "3") (pinfunction "S_3") (pintype "passive"))
      (node (ref "U.YY1") (pin "13") (pinfunction "VIN1_13") (pintype "input"))
    )
    (net (code "38") (name "Net-(Q.YY1B-D)") (class "Default")
      (node (ref "C.YY3") (pin "1") (pinfunction "1_1") (pintype "passive"))
      (node (ref "Q.YY1") (pin "D$2A") (pinfunction "D_D$2A") (pintype "passive"))
      (node (ref "Q.YY2") (pin "1") (pinfunction "S_1") (pintype "passive"))
      (node (ref "U.YY1") (pin "4") (pinfunction "VIN2_4") (pintype "input"))
    )
    (net (code "39") (name "Net-(Q.YY2A-G)") (class "Default")
      (node (ref "Q.YY2") (pin "2") (pinfunction "G_2") (pintype "passive"))
      (node (ref "U.YY1") (pin "5") (pinfunction "GATE2_5") (pintype "output"))
    )
    (net (code "40") (name "Net-(Q.YY2B-G)") (class "Default")
      (node (ref "Q.YY2") (pin "4") (pinfunction "G_4") (pintype "passive"))
      (node (ref "U.YY1") (pin "12") (pinfunction "GATE1_12") (pintype "output"))
    )
    (net (code "41") (name "Net-(R.BC1-Pad1)") (class "Default")
      (node (ref "R.BC1") (pin "1") (pinfunction "1_1") (pintype "passive"))
      (node (ref "R.BC2") (pin "2") (pinfunction "2_2") (pintype "passive"))
      (node (ref "U.BC1") (pin "NTC") (pinfunction "NTC_NTC") (pintype "bidirectional"))
    )
    (net (code "42") (name "Net-(SJ.BC1-Pad1)") (class "Default")
      (node (ref "SJ.BC1") (pin "1") (pinfunction "1_1") (pintype "passive"))
      (node (ref "U.BC1") (pin "SEL") (pinfunction "SEL_SEL") (pintype "bidirectional"))
    )
    (net (code "43") (name "Net-(U.DS1-3Y)") (class "Default")
      (node (ref "C.DS4*") (pin "1") (pinfunction "1_1") (pintype "passive"))
      (node (ref "R.DS1*") (pin "2") (pinfunction "2_2") (pintype "passive"))
      (node (ref "U.DS1") (pin "8") (pinfunction "3Y_8") (pintype "passive"))
    )
    (net (code "44") (name "Net-(U.DS1-4Y)") (class "Default")
      (node (ref "C.DS2*") (pin "1") (pinfunction "1_1") (pintype "passive"))
      (node (ref "R.DS2*") (pin "2") (pinfunction "2_2") (pintype "passive"))
      (node (ref "U.DS1") (pin "11") (pinfunction "4Y_11") (pintype "passive"))
    )
    (net (code "45") (name "Net-(U.DS2-BST)") (class "Default")
      (node (ref "C.DS5") (pin "1") (pinfunction "1_1") (pintype "passive"))
      (node (ref "U.DS2") (pin "6") (pinfunction "BST_6") (pintype "bidirectional"))
    )
    (net (code "46") (name "Net-(U.EC1-FB)") (class "Default")
      (node (ref "R.EC1") (pin "2") (pinfunction "2_2") (pintype "passive"))
      (node (ref "R.EC3") (pin "2") (pinfunction "2_2") (pintype "passive"))
      (node (ref "U.EC1") (pin "2") (pinfunction "FB_2") (pintype "input"))
    )
    (net (code "47") (name "Net-(U.EC1-RT_CLK)") (class "Default")
      (node (ref "R.EC2") (pin "2") (pinfunction "2_2") (pintype "passive"))
      (node (ref "U.EC1") (pin "24") (pinfunction "RT_CLK_24") (pintype "input"))
    )
    (net (code "48") (name "Net-(U.EC1-SW)") (class "Default")
      (node (ref "U.EC1") (pin "16") (pinfunction "SW_2_16") (pintype "output"))
      (node (ref "U.EC1") (pin "17") (pinfunction "SW_17") (pintype "output"))
    )
    (net (code "49") (name "Net-(U.EC1-TT)") (class "Default")
      (node (ref "R.EC4") (pin "1") (pinfunction "1_1") (pintype "passive"))
      (node (ref "U.EC1") (pin "5") (pinfunction "TT_5") (pintype "passive"))
    )
    (net (code "50") (name "Net-(U.ESP1-SCL{slash}CLK)") (class "Default")
      (node (ref "U.ESP1") (pin "20") (pinfunction "SCL/CLK_20") (pintype "bidirectional"))
      (node (ref "X.ESP1") (pin "4") (pinfunction "4_4") (pintype "passive"))
    )
    (net (code "51") (name "Net-(U.ESP1-SCS{slash}CMD)") (class "Default")
      (node (ref "U.ESP1") (pin "19") (pinfunction "SCS/CMD_19") (pintype "bidirectional"))
      (node (ref "X.ESP1") (pin "5") (pinfunction "5_5") (pintype "passive"))
    )
    (net (code "52") (name "Net-(U.ESP1-SDI{slash}SD1)") (class "Default")
      (node (ref "U.ESP1") (pin "22") (pinfunction "SDI/SD1_22") (pintype "bidirectional"))
      (node (ref "X.ESP1") (pin "2") (pinfunction "2_2") (pintype "passive"))
    )
    (net (code "53") (name "Net-(U.ESP1-SDO{slash}SD0)") (class "Default")
      (node (ref "U.ESP1") (pin "21") (pinfunction "SDO/SD0_21") (pintype "bidirectional"))
      (node (ref "X.ESP1") (pin "3") (pinfunction "3_3") (pintype "passive"))
    )
    (net (code "54") (name "Net-(U.YY1-CPO1)") (class "Default")
      (node (ref "C.YY2") (pin "1") (pinfunction "1_1") (pintype "passive"))
      (node (ref "U.YY1") (pin "11") (pinfunction "CPO1_11") (pintype "output"))
    )
    (net (code "55") (name "Net-(U.YY1-CPO2)") (class "Default")
      (node (ref "C.YY3") (pin "2") (pinfunction "2_2") (pintype "passive"))
      (node (ref "U.YY1") (pin "6") (pinfunction "CPO2_6") (pintype "output"))
    )
    (net (code "56") (name "Net-(U.YY1-VCC)") (class "Default")
      (node (ref "C.YY1") (pin "1") (pinfunction "1_1") (pintype "passive"))
      (node (ref "U.YY1") (pin "14") (pinfunction "VCC_14") (pintype "power_in"))
    )
    (net (code "57") (name "Net-(U.ZZ1-BST)") (class "Default")
      (node (ref "C.ZZ3") (pin "1") (pinfunction "1_1") (pintype "passive"))
      (node (ref "U.ZZ1") (pin "6") (pinfunction "BST_6") (pintype "bidirectional"))
    )
    (net (code "58") (name "Net-(U.ZZ1-EN)") (class "Default")
      (node (ref "C.ZZ2") (pin "1") (pinfunction "1_1") (pintype "passive"))
      (node (ref "C.ZZ5") (pin "2") (pinfunction "2_2") (pintype "passive"))
      (node (ref "Q.ZZ1") (pin "C") (pinfunction "C_C") (pintype "passive"))
      (node (ref "Q.ZZ2") (pin "C") (pinfunction "C_C") (pintype "passive"))
      (node (ref "Q.ZZ3") (pin "C") (pinfunction "C_C") (pintype "passive"))
      (node (ref "R.ZZ2") (pin "1") (pinfunction "1_1") (pintype "passive"))
      (node (ref "R.ZZ3") (pin "1") (pinfunction "1_1") (pintype "passive"))
      (node (ref "TP12") (pin "TP") (pinfunction "TP_TP") (pintype "input"))
      (node (ref "U.ZZ1") (pin "2") (pinfunction "EN_2") (pintype "bidirectional"))
      (node (ref "U.ZZ1") (pin "3") (pinfunction "VIN_3") (pintype "bidirectional"))
    )
    (net (code "59") (name "Net-(X.DS1-2)") (class "Default")
      (node (ref "R.DS1*") (pin "1") (pinfunction "1_1") (pintype "passive"))
      (node (ref "X.DS1") (pin "P$2") (pinfunction "2_P$2") (pintype "passive"))
    )
    (net (code "60") (name "Net-(X.DS1-3)") (class "Default")
      (node (ref "R.DS2*") (pin "1") (pinfunction "1_1") (pintype "passive"))
      (node (ref "X.DS1") (pin "P$3") (pinfunction "3_P$3") (pintype "passive"))
    )
    (net (code "61") (name "Net-(X.SI2-2)") (class "Default")
      (node (ref "C.SI2*") (pin "1") (pinfunction "1_1") (pintype "passive"))
      (node (ref "R.SI1*") (pin "1") (pinfunction "1_1") (pintype "passive"))
      (node (ref "X.SI2") (pin "P$2") (pinfunction "2_P$2") (pintype "passive"))
    )
    (net (code "62") (name "Net-(X.SI3-2)") (class "Default")
      (node (ref "C.SI3*") (pin "1") (pinfunction "1_1") (pintype "passive"))
      (node (ref "R.SI2*") (pin "1") (pinfunction "1_1") (pintype "passive"))
      (node (ref "X.SI3") (pin "P$2") (pinfunction "2_P$2") (pintype "passive"))
    )
    (net (code "63") (name "RAWSENSE") (class "Default")
      (node (ref "R.VI2") (pin "1") (pinfunction "1_1") (pintype "passive"))
      (node (ref "R.VI3") (pin "2") (pinfunction "2_2") (pintype "passive"))
      (node (ref "U.ESP1") (pin "6") (pinfunction "IO34_6") (pintype "bidirectional"))
    )
    (net (code "64") (name "RESET") (class "Default")
      (node (ref "R.ESP2") (pin "2") (pinfunction "2_2") (pintype "passive"))
      (node (ref "SV1") (pin "P$1") (pinfunction "1_P$1") (pintype "passive"))
      (node (ref "U.ESP1") (pin "3") (pinfunction "EN_3") (pintype "input"))
    )
    (net (code "65") (name "SERVO1") (class "Default")
      (node (ref "R.SI1*") (pin "2") (pinfunction "2_2") (pintype "passive"))
      (node (ref "U.ESP1") (pin "37") (pinfunction "IO23_37") (pintype "bidirectional"))
    )
    (net (code "66") (name "SERVO2") (class "Default")
      (node (ref "R.SI2*") (pin "2") (pinfunction "2_2") (pintype "passive"))
      (node (ref "U.ESP1") (pin "10") (pinfunction "IO25_10") (pintype "bidirectional"))
    )
    (net (code "67") (name "SYS_POWER") (class "Default")
      (node (ref "C.DS7") (pin "1") (pinfunction "1_1") (pintype "passive"))
      (node (ref "C.DS9") (pin "2") (pinfunction "2_2") (pintype "passive"))
      (node (ref "C.SI1") (pin "2") (pinfunction "2_2") (pintype "passive"))
      (node (ref "C.YY4") (pin "1") (pinfunction "1_1") (pintype "passive"))
      (node (ref "Q.YY2") (pin "5") (pinfunction "D_5") (pintype "passive"))
      (node (ref "Q.YY2") (pin "6") (pinfunction "D_6") (pintype "passive"))
      (node (ref "Q.YY2") (pin "7") (pinfunction "D_7") (pintype "passive"))
      (node (ref "Q.YY2") (pin "8") (pinfunction "D_8") (pintype "passive"))
      (node (ref "R.YY2") (pin "2") (pinfunction "2_2") (pintype "passive"))
      (node (ref "U.DS2") (pin "2") (pinfunction "EN_2") (pintype "bidirectional"))
      (node (ref "U.DS2") (pin "3") (pinfunction "VIN_3") (pintype "bidirectional"))
      (node (ref "U.YY1") (pin "10") (pinfunction "OUT1_10") (pintype "output"))
      (node (ref "U.YY1") (pin "7") (pinfunction "OUT2_7") (pintype "output"))
      (node (ref "X.SI1") (pin "P$2") (pinfunction "2_P$2") (pintype "passive"))
      (node (ref "X.SI2") (pin "P$1") (pinfunction "1_P$1") (pintype "passive"))
      (node (ref "X.SI3") (pin "P$1") (pinfunction "1_P$1") (pintype "passive"))
    )
    (net (code "68") (name "SYS_SENSE") (class "Default")
      (node (ref "R.YY1") (pin "2") (pinfunction "2_2") (pintype "passive"))
      (node (ref "R.YY2") (pin "1") (pinfunction "1_1") (pintype "passive"))
      (node (ref "U.ESP1") (pin "7") (pinfunction "IO35_7") (pintype "bidirectional"))
    )
    (net (code "69") (name "TACH") (class "Default")
      (node (ref "C.VI2*") (pin "1") (pinfunction "1_1") (pintype "passive"))
      (node (ref "R.VI4") (pin "1") (pinfunction "1_1") (pintype "passive"))
      (node (ref "R.VI5") (pin "2") (pinfunction "2_2") (pintype "passive"))
      (node (ref "U.ESP1") (pin "27") (pinfunction "IO16_27") (pintype "bidirectional"))
    )
    (net (code "70") (name "VBAT") (class "Default")
      (node (ref "C.BC4") (pin "1") (pinfunction "1_1") (pintype "passive"))
      (node (ref "C.BI1") (pin "1") (pinfunction "1_1") (pintype "passive"))
      (node (ref "Q.BI2") (pin "2") (pinfunction "S_2") (pintype "passive"))
      (node (ref "Q.YY1") (pin "P$1") (pinfunction "S_P$1") (pintype "passive"))
      (node (ref "Q.ZZ3") (pin "A") (pinfunction "A_A") (pintype "passive"))
      (node (ref "R.BC3") (pin "2") (pinfunction "2_2") (pintype "passive"))
      (node (ref "TP1") (pin "TP") (pinfunction "TP_TP") (pintype "input"))
      (node (ref "U.BC1") (pin "BAT") (pinfunction "BAT_BAT") (pintype "bidirectional"))
      (node (ref "X.BI1") (pin "1") (pinfunction "1_1") (pintype "passive"))
    )
    (net (code "71") (name "VCONV") (class "Default")
      (node (ref "C.EC5") (pin "1") (pinfunction "1_1") (pintype "passive"))
      (node (ref "C.EC6") (pin "P$2") (pinfunction "+_P$2") (pintype "passive"))
      (node (ref "C.EC7") (pin "2") (pinfunction "2_2") (pintype "passive"))
      (node (ref "Q.YY1") (pin "P$3") (pinfunction "S_P$3") (pintype "passive"))
      (node (ref "Q.ZZ1") (pin "A") (pinfunction "A_A") (pintype "passive"))
      (node (ref "R.EC1") (pin "1") (pinfunction "1_1") (pintype "passive"))
      (node (ref "TP4") (pin "TP") (pinfunction "TP_TP") (pintype "input"))
      (node (ref "U.EC1") (pin "1") (pinfunction "VOUT_2_1") (pintype "power_in"))
      (node (ref "U.EC1") (pin "8") (pinfunction "VOUT_8") (pintype "power_in"))
    )
    (net (code "72") (name "VPROG") (class "Default")
      (node (ref "Q.DS1") (pin "A") (pinfunction "A_A") (pintype "passive"))
      (node (ref "Q.ZZ2") (pin "A") (pinfunction "A_A") (pintype "passive"))
      (node (ref "SV1") (pin "P$6") (pinfunction "6_P$6") (pintype "passive"))
    )
    (net (code "73") (name "VRAW") (class "Default")
      (node (ref "C.BC3") (pin "1") (pinfunction "1_1") (pintype "passive"))
      (node (ref "C.EC1") (pin "2") (pinfunction "2_2") (pintype "passive"))
      (node (ref "C.EC2") (pin "2") (pinfunction "2_2") (pintype "passive"))
      (node (ref "C.EC3") (pin "+") (pinfunction "+_+") (pintype "passive"))
      (node (ref "C.EC4") (pin "+") (pinfunction "+_+") (pintype "passive"))
      (node (ref "C.VI3") (pin "1") (pinfunction "1_1") (pintype "passive"))
      (node (ref "Q.VI1") (pin "1") (pinfunction "K2_1") (pintype "passive"))
      (node (ref "R.VI1") (pin "2") (pinfunction "2_2") (pintype "passive"))
      (node (ref "R.VI2") (pin "2") (pinfunction "2_2") (pintype "passive"))
      (node (ref "U.BC1") (pin "VIN") (pinfunction "VIN_VIN") (pintype "bidirectional"))
      (node (ref "U.EC1") (pin "11") (pinfunction "VIN_2_11") (pintype "power_in"))
      (node (ref "U.EC1") (pin "22") (pinfunction "VIN_22") (pintype "power_in"))
      (node (ref "X.VI1") (pin "2") (pinfunction "2_2") (pintype "passive"))
    )
    (net (code "74") (name "unconnected-(SV1-4-PadP$4)") (class "Default")
      (node (ref "SV1") (pin "P$4") (pinfunction "4_P$4") (pintype "passive"))
    )
    (net (code "75") (name "unconnected-(U.BC1-PadCELL)") (class "Default")
      (node (ref "U.BC1") (pin "CELL") (pinfunction "CELL_CELL") (pintype "bidirectional"))
    )
    (net (code "76") (name "unconnected-(U.BC1-~{EN}-Pad!EN)") (class "Default")
      (node (ref "U.BC1") (pin "!EN") (pinfunction "~{EN}_!EN") (pintype "bidirectional"))
    )
    (net (code "77") (name "unconnected-(U.DS1-1Y-Pad3)") (class "Default")
      (node (ref "U.DS1") (pin "3") (pinfunction "1Y_3") (pintype "passive"))
    )
    (net (code "78") (name "unconnected-(U.DS1-2Y-Pad6)") (class "Default")
      (node (ref "U.DS1") (pin "6") (pinfunction "2Y_6") (pintype "passive"))
    )
    (net (code "79") (name "unconnected-(U.EC1-DNC-Pad4)") (class "Default")
      (node (ref "U.EC1") (pin "4") (pinfunction "DNC_4") (pintype "passive"))
    )
    (net (code "80") (name "unconnected-(U.EC1-EN-Pad10)") (class "Default")
      (node (ref "U.EC1") (pin "10") (pinfunction "EN_10") (pintype "input"))
    )
    (net (code "81") (name "unconnected-(U.EC1-PGOOD-Pad7)") (class "Default")
      (node (ref "U.EC1") (pin "7") (pinfunction "PGOOD_7") (pintype "passive"))
    )
    (net (code "82") (name "unconnected-(U.EC1-SS_TRK-Pad6)") (class "Default")
      (node (ref "U.EC1") (pin "6") (pinfunction "SS_TRK_6") (pintype "passive"))
    )
    (net (code "83") (name "unconnected-(U.ESP1-IO2-Pad24)") (class "Default")
      (node (ref "U.ESP1") (pin "24") (pinfunction "IO2_24") (pintype "bidirectional"))
    )
    (net (code "84") (name "unconnected-(U.ESP1-IO5-Pad29)") (class "Default")
      (node (ref "U.ESP1") (pin "29") (pinfunction "IO5_29") (pintype "bidirectional"))
    )
    (net (code "85") (name "unconnected-(U.ESP1-IO14-Pad13)") (class "Default")
      (node (ref "U.ESP1") (pin "13") (pinfunction "IO14_13") (pintype "bidirectional"))
    )
    (net (code "86") (name "unconnected-(U.ESP1-IO15-Pad23)") (class "Default")
      (node (ref "U.ESP1") (pin "23") (pinfunction "IO15_23") (pintype "bidirectional"))
    )
    (net (code "87") (name "unconnected-(U.ESP1-IO18-Pad30)") (class "Default")
      (node (ref "U.ESP1") (pin "30") (pinfunction "IO18_30") (pintype "bidirectional"))
    )
    (net (code "88") (name "unconnected-(U.ESP1-IO20-Pad32)") (class "Default")
      (node (ref "U.ESP1") (pin "32") (pinfunction "IO20_32") (pintype "bidirectional"))
    )
    (net (code "89") (name "unconnected-(U.ESP1-IO32-Pad8)") (class "Default")
      (node (ref "U.ESP1") (pin "8") (pinfunction "IO32_8") (pintype "bidirectional"))
    )
    (net (code "90") (name "unconnected-(U.ESP1-IO33-Pad9)") (class "Default")
      (node (ref "U.ESP1") (pin "9") (pinfunction "IO33_9") (pintype "bidirectional"))
    )
    (net (code "91") (name "unconnected-(U.ESP1-SHD{slash}SD2-Pad17)") (class "Default")
      (node (ref "U.ESP1") (pin "17") (pinfunction "SHD/SD2_17") (pintype "bidirectional"))
    )
    (net (code "92") (name "unconnected-(U.ESP1-SWP{slash}SD3-Pad18)") (class "Default")
      (node (ref "U.ESP1") (pin "18") (pinfunction "SWP/SD3_18") (pintype "bidirectional"))
    )
    (net (code "93") (name "unconnected-(U.YY1-NC-Pad3)") (class "Default")
      (node (ref "U.YY1") (pin "3") (pinfunction "NC_3") (pintype "no_connect"))
    )
    (net (code "94") (name "unconnected-(U.YY1-NC_2-Pad2)") (class "Default")
      (node (ref "U.YY1") (pin "2") (pinfunction "NC_2_2") (pintype "no_connect"))
    )
  )
)
